# Hephaestus_v1_5.net
KiCad netlist of a schematic drawn in EAGLE
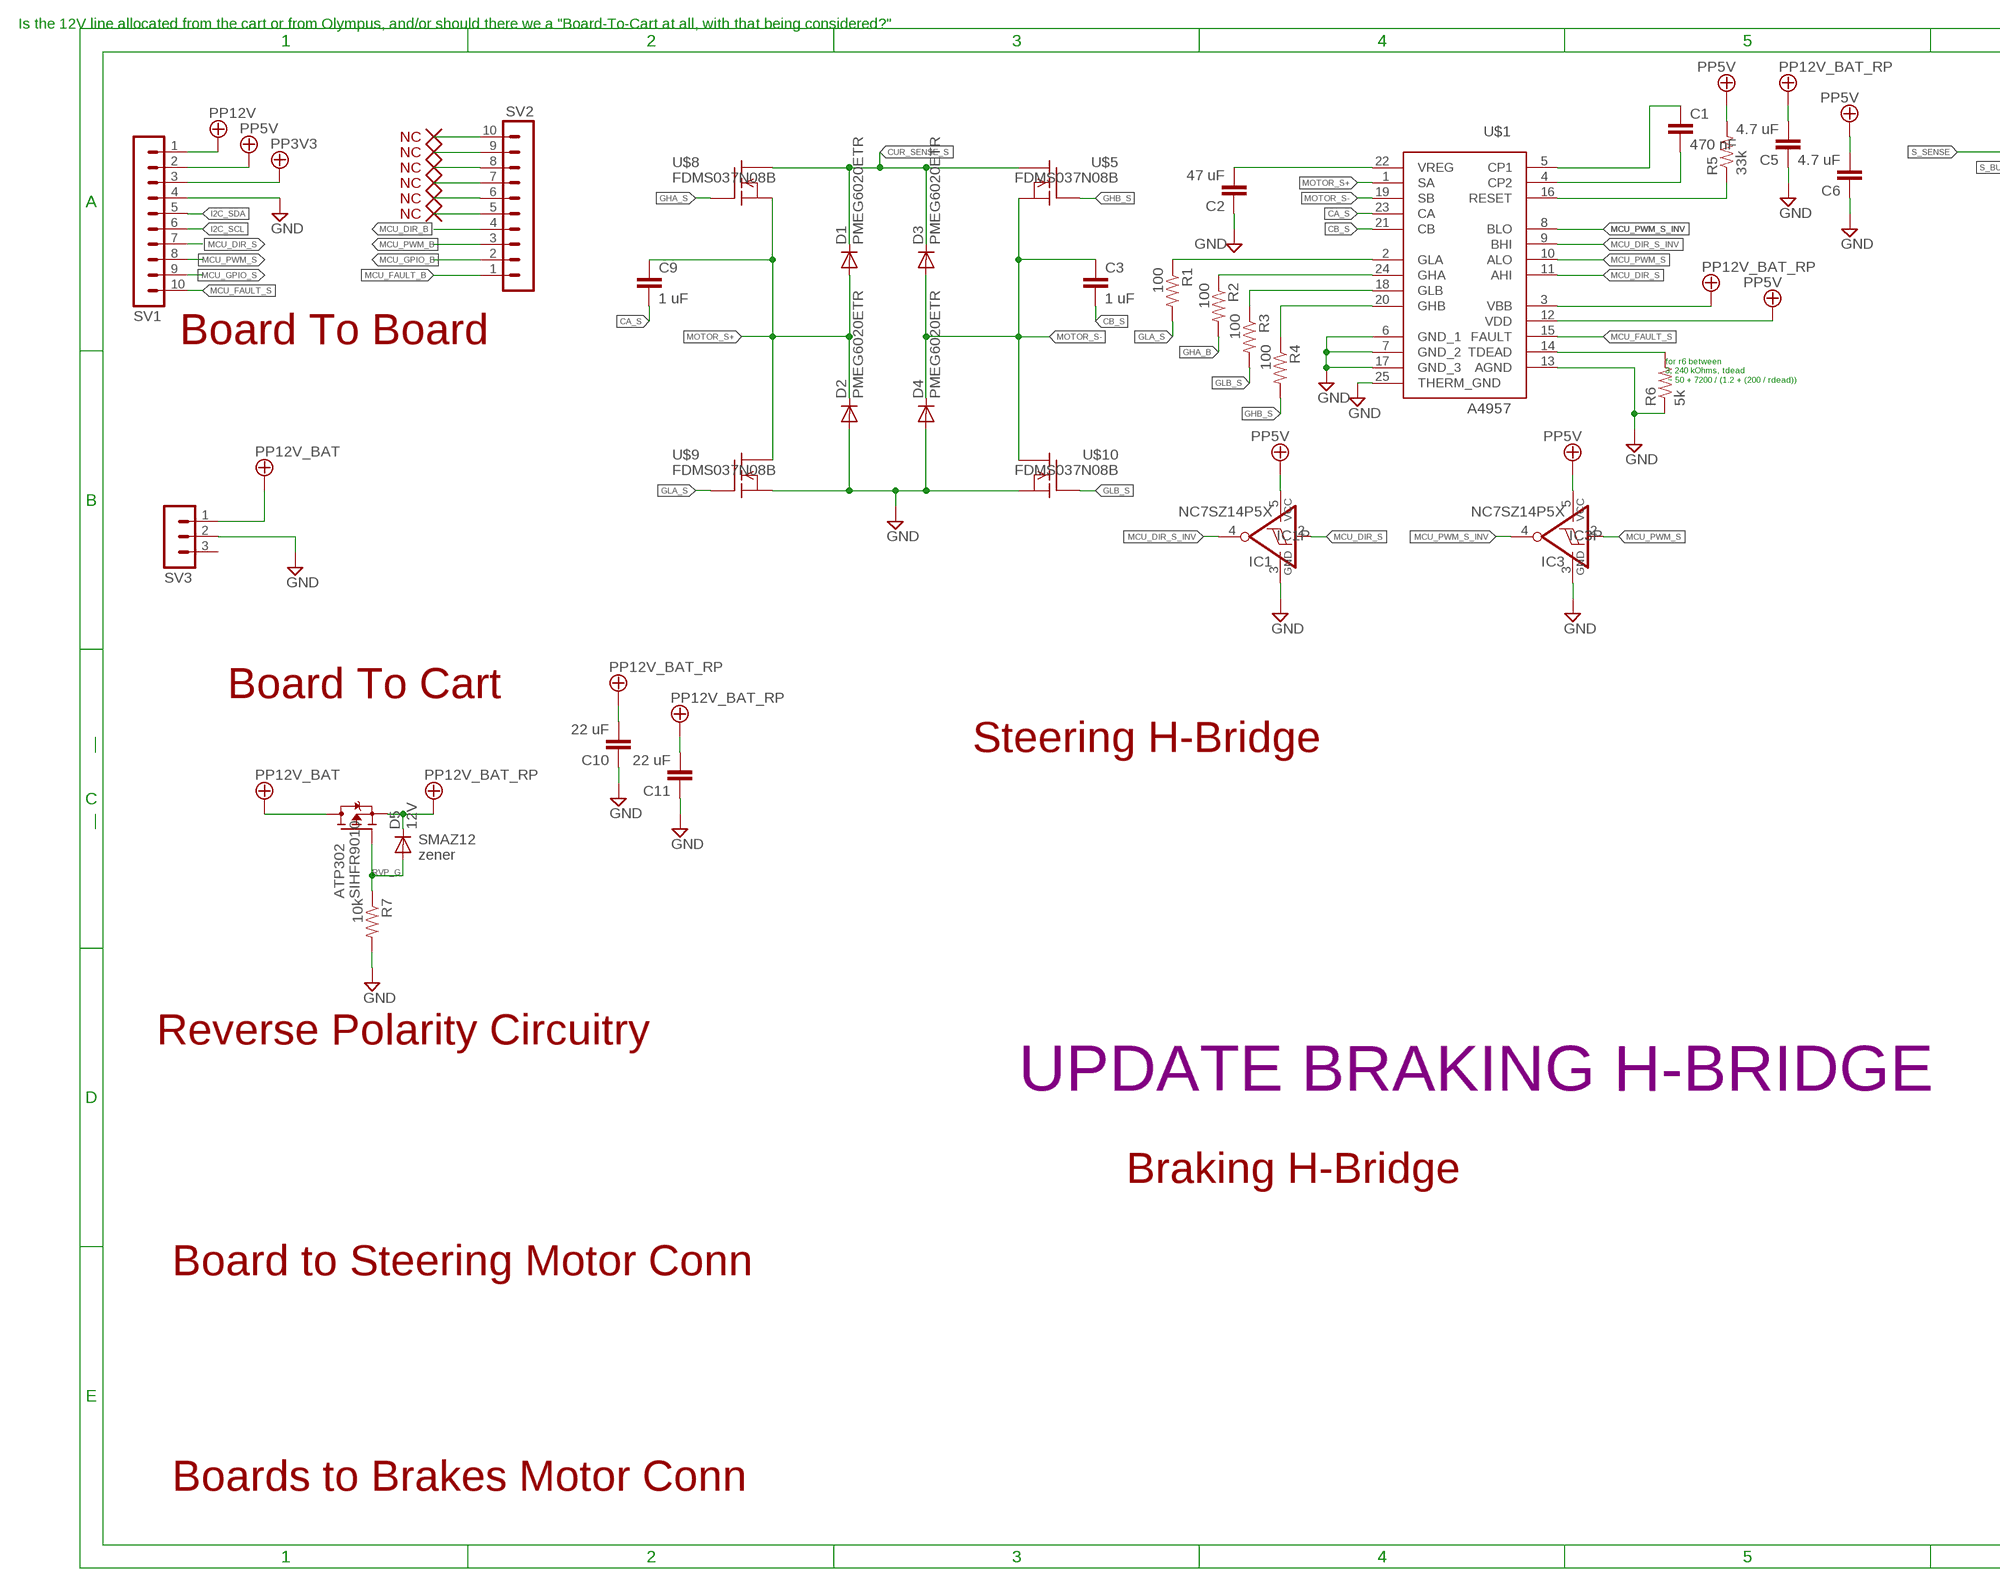
[diagram p0: schematic, sheet 1, part 1 of 2]
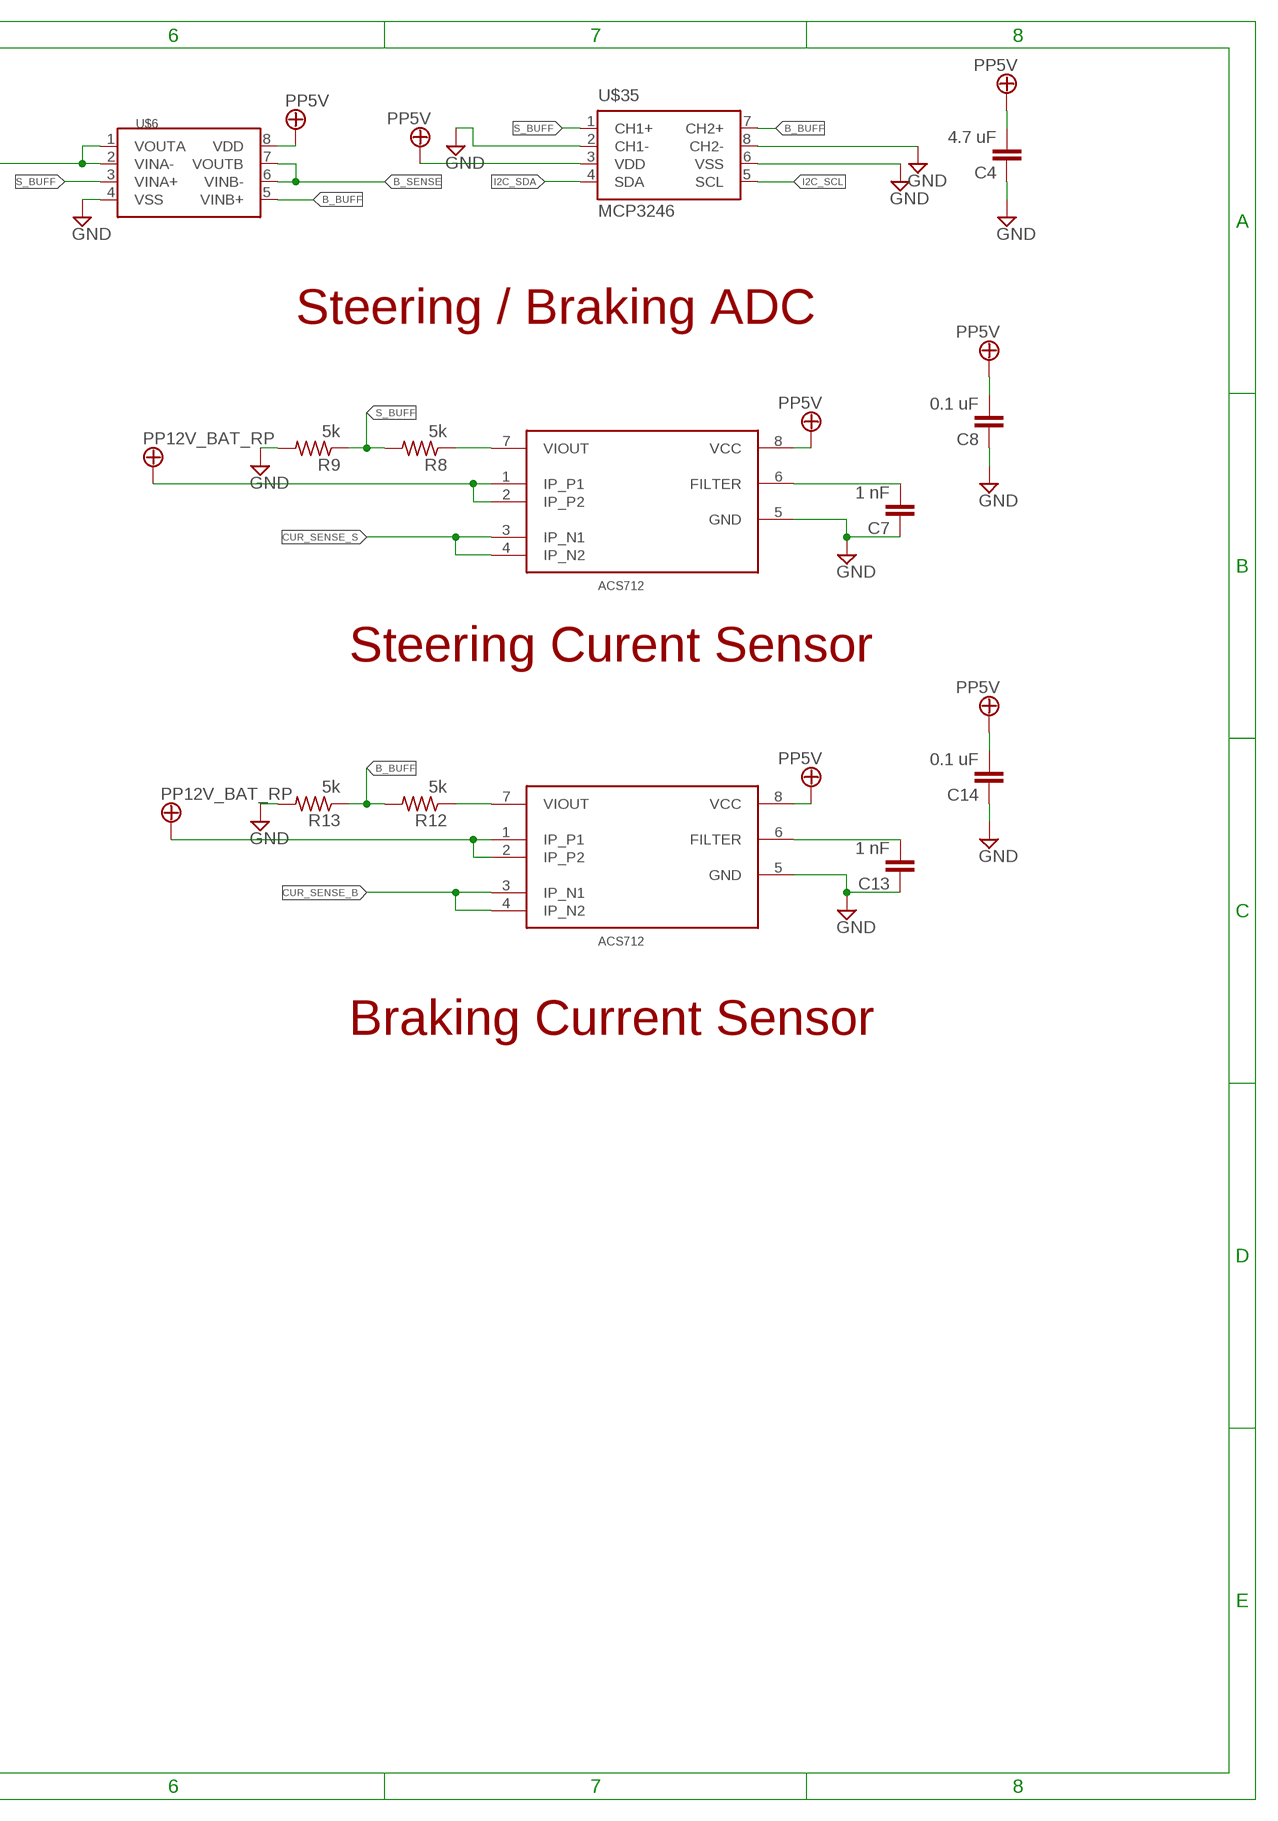
[diagram p1: schematic, sheet 1, part 2 of 2]

(export (version "E")
  (design (tool "Eeschema 10.0.6"))
  (components
    (comp (ref "ACS1")
      (value "ACS712")
      (footprint "eagle-import:SOIC-08")
      (libsource (lib "eagle-import") (part "ACS712"))
    )
    (comp (ref "ACS712")
      (value "ACS712")
      (footprint "eagle-import:SOIC-08")
      (libsource (lib "eagle-import") (part "ACS712"))
    )
    (comp (ref "C1")
      (value "470 nF")
      (footprint "eagle-import:C0603")
      (libsource (lib "eagle-import") (part "CC0603"))
    )
    (comp (ref "C2")
      (value "47 uF")
      (footprint "eagle-import:C0603")
      (libsource (lib "eagle-import") (part "CC0603"))
    )
    (comp (ref "C3")
      (value "1 uF")
      (footprint "eagle-import:C0603")
      (libsource (lib "eagle-import") (part "CC0603"))
    )
    (comp (ref "C4")
      (value "4.7 uF")
      (footprint "eagle-import:C0603")
      (libsource (lib "eagle-import") (part "CC0603"))
    )
    (comp (ref "C5")
      (value "4.7 uF")
      (footprint "eagle-import:C0603")
      (libsource (lib "eagle-import") (part "CC0603"))
    )
    (comp (ref "C6")
      (value "4.7 uF")
      (footprint "eagle-import:C0603")
      (libsource (lib "eagle-import") (part "CC0603"))
    )
    (comp (ref "C7")
      (value "1 nF")
      (footprint "eagle-import:C0603")
      (libsource (lib "eagle-import") (part "CC0603"))
    )
    (comp (ref "C8")
      (value "0.1 uF")
      (footprint "eagle-import:C0603")
      (libsource (lib "eagle-import") (part "CC0603"))
    )
    (comp (ref "C9")
      (value "1 uF")
      (footprint "eagle-import:C0603")
      (libsource (lib "eagle-import") (part "CC0603"))
    )
    (comp (ref "C10")
      (value "22 uF")
      (footprint "eagle-import:C0603")
      (libsource (lib "eagle-import") (part "CC0603"))
    )
    (comp (ref "C11")
      (value "22 uF")
      (footprint "eagle-import:C0603")
      (libsource (lib "eagle-import") (part "CC0603"))
    )
    (comp (ref "C13")
      (value "1 nF")
      (footprint "eagle-import:C0603")
      (libsource (lib "eagle-import") (part "CC0603"))
    )
    (comp (ref "C14")
      (value "0.1 uF")
      (footprint "eagle-import:C0603")
      (libsource (lib "eagle-import") (part "CC0603"))
    )
    (comp (ref "D1")
      (value "PMEG6020ETR")
      (footprint "eagle-import:SOD123FL")
      (libsource (lib "eagle-import") (part "PMEG6020ETR"))
    )
    (comp (ref "D2")
      (value "PMEG6020ETR")
      (footprint "eagle-import:SOD123FL")
      (libsource (lib "eagle-import") (part "PMEG6020ETR"))
    )
    (comp (ref "D3")
      (value "PMEG6020ETR")
      (footprint "eagle-import:SOD123FL")
      (libsource (lib "eagle-import") (part "PMEG6020ETR"))
    )
    (comp (ref "D4")
      (value "PMEG6020ETR")
      (footprint "eagle-import:SOD123FL")
      (libsource (lib "eagle-import") (part "PMEG6020ETR"))
    )
    (comp (ref "D5")
      (value "12V")
      (footprint "eagle-import:DO214AC")
      (libsource (lib "eagle-import") (part "DIODE-DO214AC"))
    )
    (comp (ref "IC1")
      (value "NC7SZ14P5X")
      (footprint "eagle-import:SC70-5")
      (libsource (lib "eagle-import") (part "NC7SZ14P5X"))
    )
    (comp (ref "IC3")
      (value "NC7SZ14P5X")
      (footprint "eagle-import:SC70-5")
      (libsource (lib "eagle-import") (part "NC7SZ14P5X"))
    )
    (comp (ref "R1")
      (value "100")
      (footprint "eagle-import:R0603")
      (libsource (lib "eagle-import") (part "R-US_R0603"))
    )
    (comp (ref "R2")
      (value "100")
      (footprint "eagle-import:R0603")
      (libsource (lib "eagle-import") (part "R-US_R0603"))
    )
    (comp (ref "R3")
      (value "100")
      (footprint "eagle-import:R0603")
      (libsource (lib "eagle-import") (part "R-US_R0603"))
    )
    (comp (ref "R4")
      (value "100")
      (footprint "eagle-import:R0603")
      (libsource (lib "eagle-import") (part "R-US_R0603"))
    )
    (comp (ref "R5")
      (value "33k")
      (footprint "eagle-import:R0603")
      (libsource (lib "eagle-import") (part "R-US_R0603"))
    )
    (comp (ref "R6")
      (value "5k")
      (footprint "eagle-import:R0603")
      (libsource (lib "eagle-import") (part "R-US_R0603"))
    )
    (comp (ref "R7")
      (value "10k")
      (footprint "eagle-import:R0603")
      (libsource (lib "eagle-import") (part "R-US_R0603"))
    )
    (comp (ref "R8")
      (value "5k")
      (footprint "eagle-import:R0603")
      (libsource (lib "eagle-import") (part "R-US_R0603"))
    )
    (comp (ref "R9")
      (value "5k")
      (footprint "eagle-import:R0603")
      (libsource (lib "eagle-import") (part "R-US_R0603"))
    )
    (comp (ref "R12")
      (value "5k")
      (footprint "eagle-import:R0603")
      (libsource (lib "eagle-import") (part "R-US_R0603"))
    )
    (comp (ref "R13")
      (value "5k")
      (footprint "eagle-import:R0603")
      (libsource (lib "eagle-import") (part "R-US_R0603"))
    )
    (comp (ref "SIHFR9010")
      (value "ATP302")
      (footprint "eagle-import:TO252")
      (libsource (lib "eagle-import") (part "ATP302"))
    )
    (comp (ref "SV1")
      (value "MA10-1")
      (footprint "eagle-import:MA10-1")
      (libsource (lib "eagle-import") (part "MA10-1"))
    )
    (comp (ref "SV2")
      (value "MA10-1")
      (footprint "eagle-import:MA10-1")
      (libsource (lib "eagle-import") (part "MA10-1"))
    )
    (comp (ref "SV3")
      (value "MA03-1")
      (footprint "eagle-import:MA03-1")
      (libsource (lib "eagle-import") (part "MA03-1"))
    )
    (comp (ref "U$1")
      (value "A4957")
      (footprint "eagle-import:24-WFQFN")
      (libsource (lib "eagle-import") (part "A4957"))
    )
    (comp (ref "U$5")
      (value "FDMS037N08B")
      (footprint "eagle-import:TO252")
      (libsource (lib "eagle-import") (part "FDMS037N08B"))
    )
    (comp (ref "U$6")
      (value "MCP6L02")
      (footprint "eagle-import:SOIC-08")
      (libsource (lib "eagle-import") (part "MCP6L02"))
    )
    (comp (ref "U$8")
      (value "FDMS037N08B")
      (footprint "eagle-import:TO252")
      (libsource (lib "eagle-import") (part "FDMS037N08B"))
    )
    (comp (ref "U$9")
      (value "FDMS037N08B")
      (footprint "eagle-import:TO252")
      (libsource (lib "eagle-import") (part "FDMS037N08B"))
    )
    (comp (ref "U$10")
      (value "FDMS037N08B")
      (footprint "eagle-import:TO252")
      (libsource (lib "eagle-import") (part "FDMS037N08B"))
    )
    (comp (ref "U$35")
      (value "MCP3246")
      (footprint "eagle-import:MSOP8")
      (libsource (lib "eagle-import") (part "MCP3246"))
    )
  )
  (nets
    (net (code "1") (name "/RVP_G") (class "Default")
      (node (ref "D5") (pin "A") (pinfunction "A_A") (pintype "passive"))
      (node (ref "R7") (pin "1") (pinfunction "1_1") (pintype "passive"))
      (node (ref "SIHFR9010") (pin "2") (pinfunction "G_2") (pintype "passive"))
    )
    (net (code "2") (name "B_BUFF") (class "Default")
      (node (ref "R12") (pin "2") (pinfunction "2_2") (pintype "passive"))
      (node (ref "R13") (pin "1") (pinfunction "1_1") (pintype "passive"))
      (node (ref "U$35") (pin "7") (pinfunction "CH2+_7") (pintype "input"))
      (node (ref "U$6") (pin "5") (pinfunction "VINB+_5") (pintype "bidirectional"))
    )
    (net (code "3") (name "B_SENSE") (class "Default")
      (node (ref "U$6") (pin "6") (pinfunction "VINB-_6") (pintype "bidirectional"))
      (node (ref "U$6") (pin "7") (pinfunction "VOUTB_7") (pintype "bidirectional"))
    )
    (net (code "4") (name "CA_S") (class "Default")
      (node (ref "C9") (pin "2") (pinfunction "2_2") (pintype "passive"))
      (node (ref "U$1") (pin "23") (pinfunction "CA_23") (pintype "bidirectional"))
    )
    (net (code "5") (name "CB_S") (class "Default")
      (node (ref "C3") (pin "2") (pinfunction "2_2") (pintype "passive"))
      (node (ref "U$1") (pin "21") (pinfunction "CB_21") (pintype "bidirectional"))
    )
    (net (code "6") (name "CUR_SENSE_B") (class "Default")
      (node (ref "ACS1") (pin "3") (pinfunction "IP_N1_3") (pintype "bidirectional"))
      (node (ref "ACS1") (pin "4") (pinfunction "IP_N2_4") (pintype "bidirectional"))
    )
    (net (code "7") (name "CUR_SENSE_S") (class "Default")
      (node (ref "ACS712") (pin "3") (pinfunction "IP_N1_3") (pintype "bidirectional"))
      (node (ref "ACS712") (pin "4") (pinfunction "IP_N2_4") (pintype "bidirectional"))
      (node (ref "D1") (pin "C") (pinfunction "C_C") (pintype "passive"))
      (node (ref "D3") (pin "C") (pinfunction "C_C") (pintype "passive"))
      (node (ref "U$5") (pin "1") (pinfunction "D_1") (pintype "passive"))
      (node (ref "U$8") (pin "1") (pinfunction "D_1") (pintype "passive"))
    )
    (net (code "8") (name "GHA_B") (class "Default")
      (node (ref "R2") (pin "2") (pinfunction "2_2") (pintype "passive"))
    )
    (net (code "9") (name "GHA_S") (class "Default")
      (node (ref "U$8") (pin "2") (pinfunction "G_2") (pintype "passive"))
    )
    (net (code "10") (name "GHB_S") (class "Default")
      (node (ref "R4") (pin "2") (pinfunction "2_2") (pintype "passive"))
      (node (ref "U$5") (pin "2") (pinfunction "G_2") (pintype "passive"))
    )
    (net (code "11") (name "GLA_S") (class "Default")
      (node (ref "R1") (pin "2") (pinfunction "2_2") (pintype "passive"))
      (node (ref "U$9") (pin "2") (pinfunction "G_2") (pintype "passive"))
    )
    (net (code "12") (name "GLB_S") (class "Default")
      (node (ref "R3") (pin "2") (pinfunction "2_2") (pintype "passive"))
      (node (ref "U$10") (pin "2") (pinfunction "G_2") (pintype "passive"))
    )
    (net (code "13") (name "GND") (class "Default")
      (node (ref "ACS1") (pin "5") (pinfunction "GND_5") (pintype "bidirectional"))
      (node (ref "ACS712") (pin "5") (pinfunction "GND_5") (pintype "bidirectional"))
      (node (ref "C10") (pin "1") (pinfunction "1_1") (pintype "passive"))
      (node (ref "C11") (pin "1") (pinfunction "1_1") (pintype "passive"))
      (node (ref "C13") (pin "1") (pinfunction "1_1") (pintype "passive"))
      (node (ref "C14") (pin "1") (pinfunction "1_1") (pintype "passive"))
      (node (ref "C2") (pin "1") (pinfunction "1_1") (pintype "passive"))
      (node (ref "C4") (pin "1") (pinfunction "1_1") (pintype "passive"))
      (node (ref "C5") (pin "1") (pinfunction "1_1") (pintype "passive"))
      (node (ref "C6") (pin "1") (pinfunction "1_1") (pintype "passive"))
      (node (ref "C7") (pin "1") (pinfunction "1_1") (pintype "passive"))
      (node (ref "C8") (pin "1") (pinfunction "1_1") (pintype "passive"))
      (node (ref "D2") (pin "A") (pinfunction "A_A") (pintype "passive"))
      (node (ref "D4") (pin "A") (pinfunction "A_A") (pintype "passive"))
      (node (ref "IC1") (pin "3") (pinfunction "GND_3") (pintype "power_in"))
      (node (ref "IC3") (pin "3") (pinfunction "GND_3") (pintype "power_in"))
      (node (ref "R13") (pin "2") (pinfunction "2_2") (pintype "passive"))
      (node (ref "R6") (pin "1") (pinfunction "1_1") (pintype "passive"))
      (node (ref "R7") (pin "2") (pinfunction "2_2") (pintype "passive"))
      (node (ref "R9") (pin "2") (pinfunction "2_2") (pintype "passive"))
      (node (ref "SV1") (pin "4") (pinfunction "4_4") (pintype "passive"))
      (node (ref "SV3") (pin "2") (pinfunction "2_2") (pintype "passive"))
      (node (ref "U$1") (pin "13") (pinfunction "AGND_13") (pintype "bidirectional"))
      (node (ref "U$1") (pin "17") (pinfunction "GND_3_17") (pintype "bidirectional"))
      (node (ref "U$1") (pin "25") (pinfunction "THERM_GND_25") (pintype "bidirectional"))
      (node (ref "U$1") (pin "6") (pinfunction "GND_1_6") (pintype "bidirectional"))
      (node (ref "U$1") (pin "7") (pinfunction "GND_2_7") (pintype "bidirectional"))
      (node (ref "U$10") (pin "3") (pinfunction "S_3") (pintype "passive"))
      (node (ref "U$35") (pin "2") (pinfunction "CH1-_2") (pintype "input"))
      (node (ref "U$35") (pin "6") (pinfunction "VSS_6") (pintype "power_in"))
      (node (ref "U$35") (pin "8") (pinfunction "CH2-_8") (pintype "input"))
      (node (ref "U$6") (pin "4") (pinfunction "VSS_4") (pintype "bidirectional"))
      (node (ref "U$9") (pin "3") (pinfunction "S_3") (pintype "passive"))
    )
    (net (code "14") (name "I2C_SCL") (class "Default")
      (node (ref "SV1") (pin "6") (pinfunction "6_6") (pintype "passive"))
      (node (ref "U$35") (pin "5") (pinfunction "SCL_5") (pintype "bidirectional"))
    )
    (net (code "15") (name "I2C_SDA") (class "Default")
      (node (ref "SV1") (pin "5") (pinfunction "5_5") (pintype "passive"))
      (node (ref "U$35") (pin "4") (pinfunction "SDA_4") (pintype "bidirectional"))
    )
    (net (code "16") (name "MCU_DIR_B") (class "Default")
      (node (ref "SV2") (pin "4") (pinfunction "4_4") (pintype "passive"))
    )
    (net (code "17") (name "MCU_DIR_S") (class "Default")
      (node (ref "IC1") (pin "2") (pinfunction "I_2") (pintype "input"))
      (node (ref "SV1") (pin "7") (pinfunction "7_7") (pintype "passive"))
      (node (ref "U$1") (pin "11") (pinfunction "AHI_11") (pintype "bidirectional"))
    )
    (net (code "18") (name "MCU_DIR_S_INV") (class "Default")
      (node (ref "IC1") (pin "4") (pinfunction "O_4") (pintype "output"))
      (node (ref "U$1") (pin "9") (pinfunction "BHI_9") (pintype "bidirectional"))
    )
    (net (code "19") (name "MCU_FAULT_B") (class "Default")
      (node (ref "SV2") (pin "1") (pinfunction "1_1") (pintype "passive"))
    )
    (net (code "20") (name "MCU_FAULT_S") (class "Default")
      (node (ref "SV1") (pin "10") (pinfunction "10_10") (pintype "passive"))
      (node (ref "U$1") (pin "15") (pinfunction "FAULT_15") (pintype "bidirectional"))
    )
    (net (code "21") (name "MCU_GPIO_B") (class "Default")
      (node (ref "SV2") (pin "2") (pinfunction "2_2") (pintype "passive"))
    )
    (net (code "22") (name "MCU_GPIO_S") (class "Default")
      (node (ref "SV1") (pin "9") (pinfunction "9_9") (pintype "passive"))
    )
    (net (code "23") (name "MCU_PWM_B") (class "Default")
      (node (ref "SV2") (pin "3") (pinfunction "3_3") (pintype "passive"))
    )
    (net (code "24") (name "MCU_PWM_S") (class "Default")
      (node (ref "IC3") (pin "2") (pinfunction "I_2") (pintype "input"))
      (node (ref "SV1") (pin "8") (pinfunction "8_8") (pintype "passive"))
      (node (ref "U$1") (pin "10") (pinfunction "ALO_10") (pintype "bidirectional"))
    )
    (net (code "25") (name "MCU_PWM_S_INV") (class "Default")
      (node (ref "IC3") (pin "4") (pinfunction "O_4") (pintype "output"))
      (node (ref "U$1") (pin "8") (pinfunction "BLO_8") (pintype "bidirectional"))
    )
    (net (code "26") (name "MOTOR_S+") (class "Default")
      (node (ref "C9") (pin "1") (pinfunction "1_1") (pintype "passive"))
      (node (ref "D1") (pin "A") (pinfunction "A_A") (pintype "passive"))
      (node (ref "D2") (pin "C") (pinfunction "C_C") (pintype "passive"))
      (node (ref "U$1") (pin "1") (pinfunction "SA_1") (pintype "bidirectional"))
      (node (ref "U$8") (pin "3") (pinfunction "S_3") (pintype "passive"))
      (node (ref "U$9") (pin "1") (pinfunction "D_1") (pintype "passive"))
    )
    (net (code "27") (name "MOTOR_S-") (class "Default")
      (node (ref "C3") (pin "1") (pinfunction "1_1") (pintype "passive"))
      (node (ref "D3") (pin "A") (pinfunction "A_A") (pintype "passive"))
      (node (ref "D4") (pin "C") (pinfunction "C_C") (pintype "passive"))
      (node (ref "U$1") (pin "19") (pinfunction "SB_19") (pintype "bidirectional"))
      (node (ref "U$10") (pin "1") (pinfunction "D_1") (pintype "passive"))
      (node (ref "U$5") (pin "3") (pinfunction "S_3") (pintype "passive"))
    )
    (net (code "28") (name "Net-(ACS1-FILTER)") (class "Default")
      (node (ref "ACS1") (pin "6") (pinfunction "FILTER_6") (pintype "bidirectional"))
      (node (ref "C13") (pin "2") (pinfunction "2_2") (pintype "passive"))
    )
    (net (code "29") (name "Net-(ACS1-VIOUT)") (class "Default")
      (node (ref "ACS1") (pin "7") (pinfunction "VIOUT_7") (pintype "bidirectional"))
      (node (ref "R12") (pin "1") (pinfunction "1_1") (pintype "passive"))
    )
    (net (code "30") (name "Net-(ACS712-FILTER)") (class "Default")
      (node (ref "ACS712") (pin "6") (pinfunction "FILTER_6") (pintype "bidirectional"))
      (node (ref "C7") (pin "2") (pinfunction "2_2") (pintype "passive"))
    )
    (net (code "31") (name "Net-(ACS712-VIOUT)") (class "Default")
      (node (ref "ACS712") (pin "7") (pinfunction "VIOUT_7") (pintype "bidirectional"))
      (node (ref "R8") (pin "1") (pinfunction "1_1") (pintype "passive"))
    )
    (net (code "32") (name "Net-(U$1-CP1)") (class "Default")
      (node (ref "C1") (pin "1") (pinfunction "1_1") (pintype "passive"))
      (node (ref "U$1") (pin "5") (pinfunction "CP1_5") (pintype "bidirectional"))
    )
    (net (code "33") (name "Net-(U$1-CP2)") (class "Default")
      (node (ref "C1") (pin "2") (pinfunction "2_2") (pintype "passive"))
      (node (ref "U$1") (pin "4") (pinfunction "CP2_4") (pintype "bidirectional"))
    )
    (net (code "34") (name "Net-(U$1-GHA)") (class "Default")
      (node (ref "R2") (pin "1") (pinfunction "1_1") (pintype "passive"))
      (node (ref "U$1") (pin "24") (pinfunction "GHA_24") (pintype "bidirectional"))
    )
    (net (code "35") (name "Net-(U$1-GHB)") (class "Default")
      (node (ref "R4") (pin "1") (pinfunction "1_1") (pintype "passive"))
      (node (ref "U$1") (pin "20") (pinfunction "GHB_20") (pintype "bidirectional"))
    )
    (net (code "36") (name "Net-(U$1-GLA)") (class "Default")
      (node (ref "R1") (pin "1") (pinfunction "1_1") (pintype "passive"))
      (node (ref "U$1") (pin "2") (pinfunction "GLA_2") (pintype "bidirectional"))
    )
    (net (code "37") (name "Net-(U$1-GLB)") (class "Default")
      (node (ref "R3") (pin "1") (pinfunction "1_1") (pintype "passive"))
      (node (ref "U$1") (pin "18") (pinfunction "GLB_18") (pintype "bidirectional"))
    )
    (net (code "38") (name "Net-(U$1-RESET)") (class "Default")
      (node (ref "R5") (pin "1") (pinfunction "1_1") (pintype "passive"))
      (node (ref "U$1") (pin "16") (pinfunction "RESET_16") (pintype "bidirectional"))
    )
    (net (code "39") (name "Net-(U$1-TDEAD)") (class "Default")
      (node (ref "R6") (pin "2") (pinfunction "2_2") (pintype "passive"))
      (node (ref "U$1") (pin "14") (pinfunction "TDEAD_14") (pintype "bidirectional"))
    )
    (net (code "40") (name "Net-(U$1-VREG)") (class "Default")
      (node (ref "C2") (pin "2") (pinfunction "2_2") (pintype "passive"))
      (node (ref "U$1") (pin "22") (pinfunction "VREG_22") (pintype "bidirectional"))
    )
    (net (code "41") (name "PP3V3") (class "Default")
      (node (ref "SV1") (pin "3") (pinfunction "3_3") (pintype "passive"))
    )
    (net (code "42") (name "PP12V") (class "Default")
      (node (ref "ACS1") (pin "8") (pinfunction "VCC_8") (pintype "bidirectional"))
      (node (ref "ACS712") (pin "8") (pinfunction "VCC_8") (pintype "bidirectional"))
      (node (ref "C14") (pin "2") (pinfunction "2_2") (pintype "passive"))
      (node (ref "C4") (pin "2") (pinfunction "2_2") (pintype "passive"))
      (node (ref "C6") (pin "2") (pinfunction "2_2") (pintype "passive"))
      (node (ref "C8") (pin "2") (pinfunction "2_2") (pintype "passive"))
      (node (ref "IC1") (pin "5") (pinfunction "VCC_5") (pintype "power_in"))
      (node (ref "IC3") (pin "5") (pinfunction "VCC_5") (pintype "power_in"))
      (node (ref "R5") (pin "2") (pinfunction "2_2") (pintype "passive"))
      (node (ref "SV1") (pin "1") (pinfunction "1_1") (pintype "passive"))
      (node (ref "SV1") (pin "2") (pinfunction "2_2") (pintype "passive"))
      (node (ref "U$1") (pin "12") (pinfunction "VDD_12") (pintype "bidirectional"))
      (node (ref "U$35") (pin "3") (pinfunction "VDD_3") (pintype "power_in"))
      (node (ref "U$6") (pin "8") (pinfunction "VDD_8") (pintype "bidirectional"))
    )
    (net (code "43") (name "PP12V_BAT") (class "Default")
      (node (ref "ACS1") (pin "1") (pinfunction "IP_P1_1") (pintype "bidirectional"))
      (node (ref "ACS1") (pin "2") (pinfunction "IP_P2_2") (pintype "bidirectional"))
      (node (ref "ACS712") (pin "1") (pinfunction "IP_P1_1") (pintype "bidirectional"))
      (node (ref "ACS712") (pin "2") (pinfunction "IP_P2_2") (pintype "bidirectional"))
      (node (ref "C10") (pin "2") (pinfunction "2_2") (pintype "passive"))
      (node (ref "C11") (pin "2") (pinfunction "2_2") (pintype "passive"))
      (node (ref "C5") (pin "2") (pinfunction "2_2") (pintype "passive"))
      (node (ref "D5") (pin "C") (pinfunction "C_C") (pintype "passive"))
      (node (ref "SIHFR9010") (pin "1") (pinfunction "D_1") (pintype "passive"))
      (node (ref "SIHFR9010") (pin "3") (pinfunction "S_3") (pintype "passive"))
      (node (ref "SV3") (pin "1") (pinfunction "1_1") (pintype "passive"))
      (node (ref "U$1") (pin "3") (pinfunction "VBB_3") (pintype "bidirectional"))
    )
    (net (code "44") (name "S_BUFF") (class "Default")
      (node (ref "R8") (pin "2") (pinfunction "2_2") (pintype "passive"))
      (node (ref "R9") (pin "1") (pinfunction "1_1") (pintype "passive"))
      (node (ref "U$35") (pin "1") (pinfunction "CH1+_1") (pintype "input"))
      (node (ref "U$6") (pin "3") (pinfunction "VINA+_3") (pintype "bidirectional"))
    )
    (net (code "45") (name "S_SENSE") (class "Default")
      (node (ref "U$6") (pin "1") (pinfunction "VOUTA_1") (pintype "bidirectional"))
      (node (ref "U$6") (pin "2") (pinfunction "VINA-_2") (pintype "bidirectional"))
    )
    (net (code "46") (name "unconnected-(SV2-Pad5)") (class "Default")
      (node (ref "SV2") (pin "5") (pinfunction "5_5") (pintype "passive"))
    )
    (net (code "47") (name "unconnected-(SV2-Pad6)") (class "Default")
      (node (ref "SV2") (pin "6") (pinfunction "6_6") (pintype "passive"))
    )
    (net (code "48") (name "unconnected-(SV2-Pad7)") (class "Default")
      (node (ref "SV2") (pin "7") (pinfunction "7_7") (pintype "passive"))
    )
    (net (code "49") (name "unconnected-(SV2-Pad8)") (class "Default")
      (node (ref "SV2") (pin "8") (pinfunction "8_8") (pintype "passive"))
    )
    (net (code "50") (name "unconnected-(SV2-Pad9)") (class "Default")
      (node (ref "SV2") (pin "9") (pinfunction "9_9") (pintype "passive"))
    )
    (net (code "51") (name "unconnected-(SV2-Pad10)") (class "Default")
      (node (ref "SV2") (pin "10") (pinfunction "10_10") (pintype "passive"))
    )
    (net (code "52") (name "unconnected-(SV3-Pad3)") (class "Default")
      (node (ref "SV3") (pin "3") (pinfunction "3_3") (pintype "passive"))
    )
  )
)
